# 2225B_VumetreFrequenciel.net
KiCad netlist of a schematic drawn in Altium Designer
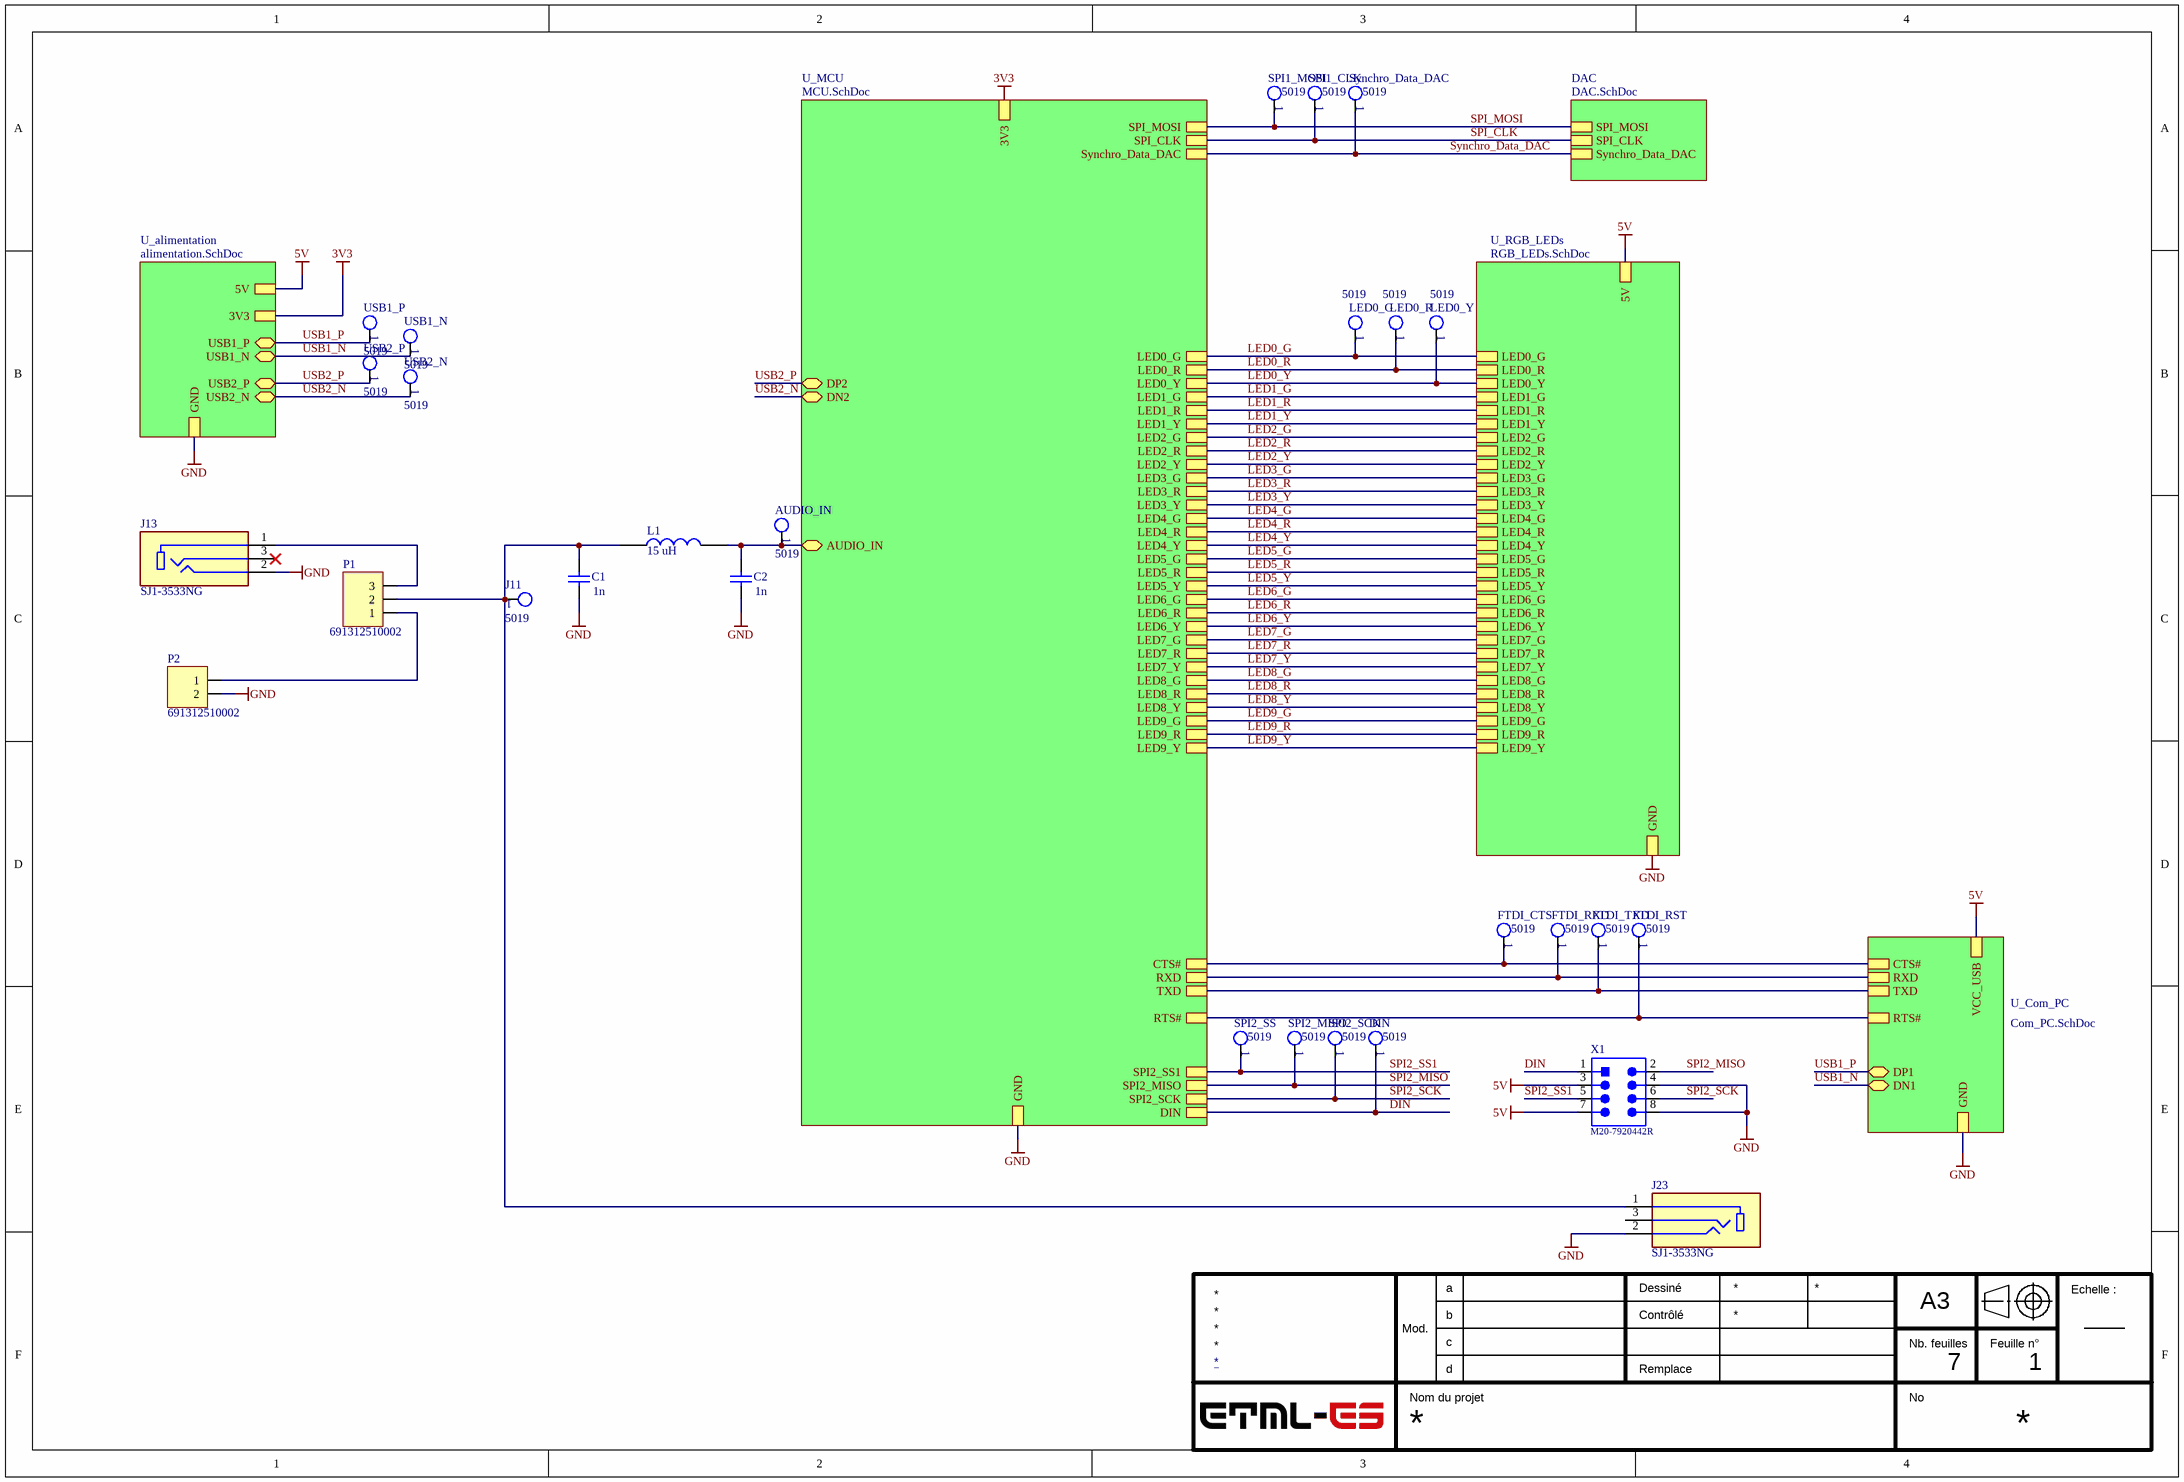
[diagram p0: 2225B_VumetreFrequenciel.SchDoc]

(export (version "E")
  (design (tool "Eeschema 10.0.6"))
  (components
    (comp (ref "AUDIO_IN")
      (value "5019")
      (footprint "KEYSTONE_5019")
      (fields (field (name "MANUFACTURER") "Keystone Electronics"))
      (libsource (lib "2225B_VumetreFrequenciel") (part "CMP-1672-00008-2"))
    )
    (comp (ref "C1")
      (value "1n")
      (footprint "C0805")
      (description "Capacitor")
      (fields (field (name "PUBLISHER") "Altium Limited"))
      (libsource (lib "Miscellaneous Devices") (part "Cap"))
    )
    (comp (ref "C2")
      (value "1n")
      (footprint "C0805")
      (description "Capacitor")
      (fields (field (name "PUBLISHER") "Altium Limited"))
      (libsource (lib "Miscellaneous Devices") (part "Cap"))
    )
    (comp (ref "DIN")
      (value "5019")
      (footprint "KEYSTONE_5019")
      (fields (field (name "MANUFACTURER") "Keystone Electronics"))
      (libsource (lib "2225B_VumetreFrequenciel") (part "CMP-1672-00008-2"))
    )
    (comp (ref "FTDI_CTS")
      (value "5019")
      (footprint "KEYSTONE_5019")
      (fields (field (name "MANUFACTURER") "Keystone Electronics"))
      (libsource (lib "2225B_VumetreFrequenciel") (part "CMP-1672-00008-2"))
    )
    (comp (ref "FTDI_RST")
      (value "5019")
      (footprint "KEYSTONE_5019")
      (fields (field (name "MANUFACTURER") "Keystone Electronics"))
      (libsource (lib "2225B_VumetreFrequenciel") (part "CMP-1672-00008-2"))
    )
    (comp (ref "FTDI_RXD")
      (value "5019")
      (footprint "KEYSTONE_5019")
      (fields (field (name "MANUFACTURER") "Keystone Electronics"))
      (libsource (lib "2225B_VumetreFrequenciel") (part "CMP-1672-00008-2"))
    )
    (comp (ref "FTDI_TXD")
      (value "5019")
      (footprint "KEYSTONE_5019")
      (fields (field (name "MANUFACTURER") "Keystone Electronics"))
      (libsource (lib "2225B_VumetreFrequenciel") (part "CMP-1672-00008-2"))
    )
    (comp (ref "J11")
      (value "5019")
      (footprint "KEYSTONE_5019")
      (fields (field (name "MANUFACTURER") "Keystone Electronics"))
      (libsource (lib "2225B_VumetreFrequenciel") (part "CMP-1672-00008-2"))
    )
    (comp (ref "J13")
      (value "SJ1-3533NG")
      (footprint "CUI_SJ1-3533NG")
      (description "3.5 mm Right-Angle Stereo Jack, 3 Pin PCB Mount, Isolated Ground")
      (fields (field (name "MF") "{'manufacturer': u'CUI'}"))
      (libsource (lib "") (part "SJ1-3533NG_1"))
    )
    (comp (ref "J23")
      (value "SJ1-3533NG")
      (footprint "CUI_SJ1-3533NG")
      (description "3.5 mm Right-Angle Stereo Jack, 3 Pin PCB Mount, Isolated Ground")
      (fields (field (name "MF") "{'manufacturer': u'CUI'}"))
      (libsource (lib "2227_BoiteBruitage") (part "SJ1-3533NG"))
    )
    (comp (ref "L1")
      (value "15 uH")
      (footprint "WE-PD_1210")
      (description "Fixed Inductors 22uH 2.80A 0.028ohms")
      (fields (field (name "MANUFACTURER_PART_NUMBER") "CDRH125NP-220MC"))
      (libsource (lib "TP2_Convertisseur_Courant") (part "CDRH125NP-220MC"))
    )
    (comp (ref "LED0_G")
      (value "5019")
      (footprint "KEYSTONE_5019")
      (fields (field (name "MANUFACTURER") "Keystone Electronics"))
      (libsource (lib "2225B_VumetreFrequenciel") (part "CMP-1672-00008-2"))
    )
    (comp (ref "LED0_R")
      (value "5019")
      (footprint "KEYSTONE_5019")
      (fields (field (name "MANUFACTURER") "Keystone Electronics"))
      (libsource (lib "2225B_VumetreFrequenciel") (part "CMP-1672-00008-2"))
    )
    (comp (ref "LED0_Y")
      (value "5019")
      (footprint "KEYSTONE_5019")
      (fields (field (name "MANUFACTURER") "Keystone Electronics"))
      (libsource (lib "2225B_VumetreFrequenciel") (part "CMP-1672-00008-2"))
    )
    (comp (ref "P1")
      (value "691312510002")
      (footprint "61300311121")
      (description "Header, 3-Pin")
      (fields (field (name "PUBLISHER") "Altium Limited"))
      (libsource (lib "2225B_VumetreFrequenciel") (part "MHDR1X3"))
    )
    (comp (ref "P2")
      (value "691312510002")
      (footprint "LINX_CONBNC002")
      (description "Header, 2-Pin")
      (fields (field (name "PUBLISHER") "Altium Limited"))
      (libsource (lib "2225B_VumetreFrequenciel") (part "MHDR1X2"))
    )
    (comp (ref "SPI1_CLK")
      (value "5019")
      (footprint "KEYSTONE_5019")
      (fields (field (name "MANUFACTURER") "Keystone Electronics"))
      (libsource (lib "2225B_VumetreFrequenciel") (part "CMP-1672-00008-2"))
    )
    (comp (ref "SPI1_MOSI")
      (value "5019")
      (footprint "KEYSTONE_5019")
      (fields (field (name "MANUFACTURER") "Keystone Electronics"))
      (libsource (lib "2225B_VumetreFrequenciel") (part "CMP-1672-00008-2"))
    )
    (comp (ref "SPI2_MISO")
      (value "5019")
      (footprint "KEYSTONE_5019")
      (fields (field (name "MANUFACTURER") "Keystone Electronics"))
      (libsource (lib "2225B_VumetreFrequenciel") (part "CMP-1672-00008-2"))
    )
    (comp (ref "SPI2_SCK")
      (value "5019")
      (footprint "KEYSTONE_5019")
      (fields (field (name "MANUFACTURER") "Keystone Electronics"))
      (libsource (lib "2225B_VumetreFrequenciel") (part "CMP-1672-00008-2"))
    )
    (comp (ref "SPI2_SS")
      (value "5019")
      (footprint "KEYSTONE_5019")
      (fields (field (name "MANUFACTURER") "Keystone Electronics"))
      (libsource (lib "2225B_VumetreFrequenciel") (part "CMP-1672-00008-2"))
    )
    (comp (ref "Synchro_Data_DAC")
      (value "5019")
      (footprint "KEYSTONE_5019")
      (fields (field (name "MANUFACTURER") "Keystone Electronics"))
      (libsource (lib "2225B_VumetreFrequenciel") (part "CMP-1672-00008-2"))
    )
    (comp (ref "USB1_N")
      (value "5019")
      (footprint "KEYSTONE_5019")
      (fields (field (name "MANUFACTURER") "Keystone Electronics"))
      (libsource (lib "2225B_VumetreFrequenciel") (part "CMP-1672-00008-2"))
    )
    (comp (ref "USB1_P")
      (value "5019")
      (footprint "KEYSTONE_5019")
      (fields (field (name "MANUFACTURER") "Keystone Electronics"))
      (libsource (lib "2225B_VumetreFrequenciel") (part "CMP-1672-00008-2"))
    )
    (comp (ref "USB2_N")
      (value "5019")
      (footprint "KEYSTONE_5019")
      (fields (field (name "MANUFACTURER") "Keystone Electronics"))
      (libsource (lib "2225B_VumetreFrequenciel") (part "CMP-1672-00008-2"))
    )
    (comp (ref "USB2_P")
      (value "5019")
      (footprint "KEYSTONE_5019")
      (fields (field (name "MANUFACTURER") "Keystone Electronics"))
      (libsource (lib "2225B_VumetreFrequenciel") (part "CMP-1672-00008-2"))
    )
    (comp (ref "X1")
      (value "M20-7920442R")
      (footprint "610108249121")
      (description "WR-PHD Pin Header, THT, pitch 2.54mm, Dual Row, Angled, 8p")
      (fields
        (field (name "MANUFACTURER PART NUMBER") "61300821021")
        (field (name "MANUFACTURER") "Wurth Elektronik")
      )
      (libsource (lib "2126_AffichageMatriciel") (part "610108249121"))
    )
  )
  (nets
    (net (code "1") (name "/AUDIO_IN") (class "Default")
      (node (ref "AUDIO_IN") (pin "1") (pinfunction "1_1") (pintype "passive"))
      (node (ref "C2") (pin "1") (pinfunction "1_1") (pintype "passive"))
      (node (ref "L1") (pin "2") (pinfunction "2_2") (pintype "passive"))
    )
    (net (code "2") (name "/CTS#") (class "Default")
      (node (ref "FTDI_CTS") (pin "1") (pinfunction "1_1") (pintype "passive"))
    )
    (net (code "3") (name "/DIN") (class "Default")
      (node (ref "DIN") (pin "1") (pinfunction "1_1") (pintype "passive"))
      (node (ref "X1") (pin "1") (pinfunction "1_1") (pintype "passive"))
    )
    (net (code "4") (name "/LED0_G") (class "Default")
      (node (ref "LED0_G") (pin "1") (pinfunction "1_1") (pintype "passive"))
    )
    (net (code "5") (name "/LED0_R") (class "Default")
      (node (ref "LED0_R") (pin "1") (pinfunction "1_1") (pintype "passive"))
    )
    (net (code "6") (name "/LED0_Y") (class "Default")
      (node (ref "LED0_Y") (pin "1") (pinfunction "1_1") (pintype "passive"))
    )
    (net (code "34") (name "/RTS#") (class "Default")
      (node (ref "FTDI_RST") (pin "1") (pinfunction "1_1") (pintype "passive"))
    )
    (net (code "35") (name "/RXD") (class "Default")
      (node (ref "FTDI_RXD") (pin "1") (pinfunction "1_1") (pintype "passive"))
    )
    (net (code "36") (name "/SPI2_MISO") (class "Default")
      (node (ref "SPI2_MISO") (pin "1") (pinfunction "1_1") (pintype "passive"))
      (node (ref "X1") (pin "2") (pinfunction "2_2") (pintype "passive"))
    )
    (net (code "37") (name "/SPI2_SCK") (class "Default")
      (node (ref "SPI2_SCK") (pin "1") (pinfunction "1_1") (pintype "passive"))
      (node (ref "X1") (pin "6") (pinfunction "6_6") (pintype "passive"))
    )
    (net (code "38") (name "/SPI2_SS1") (class "Default")
      (node (ref "SPI2_SS") (pin "1") (pinfunction "1_1") (pintype "passive"))
      (node (ref "X1") (pin "5") (pinfunction "5_5") (pintype "passive"))
    )
    (net (code "39") (name "/SPI_CLK") (class "Default")
      (node (ref "SPI1_CLK") (pin "1") (pinfunction "1_1") (pintype "passive"))
    )
    (net (code "40") (name "/SPI_MOSI") (class "Default")
      (node (ref "SPI1_MOSI") (pin "1") (pinfunction "1_1") (pintype "passive"))
    )
    (net (code "41") (name "/Synchro_Data_DAC") (class "Default")
      (node (ref "Synchro_Data_DAC") (pin "1") (pinfunction "1_1") (pintype "passive"))
    )
    (net (code "42") (name "/TXD") (class "Default")
      (node (ref "FTDI_TXD") (pin "1") (pinfunction "1_1") (pintype "passive"))
    )
    (net (code "43") (name "/USB1_N") (class "Default")
      (node (ref "USB1_N") (pin "1") (pinfunction "1_1") (pintype "passive"))
    )
    (net (code "44") (name "/USB1_P") (class "Default")
      (node (ref "USB1_P") (pin "1") (pinfunction "1_1") (pintype "passive"))
    )
    (net (code "45") (name "/USB2_N") (class "Default")
      (node (ref "USB2_N") (pin "1") (pinfunction "1_1") (pintype "passive"))
    )
    (net (code "46") (name "/USB2_P") (class "Default")
      (node (ref "USB2_P") (pin "1") (pinfunction "1_1") (pintype "passive"))
    )
    (net (code "48") (name "5V") (class "Default")
      (node (ref "X1") (pin "3") (pinfunction "3_3") (pintype "passive"))
      (node (ref "X1") (pin "7") (pinfunction "7_7") (pintype "passive"))
    )
    (net (code "49") (name "GND") (class "Default")
      (node (ref "C1") (pin "2") (pinfunction "2_2") (pintype "passive"))
      (node (ref "C2") (pin "2") (pinfunction "2_2") (pintype "passive"))
      (node (ref "J13") (pin "2") (pinfunction "2_2") (pintype "passive"))
      (node (ref "J23") (pin "2") (pinfunction "2_2") (pintype "passive"))
      (node (ref "P2") (pin "2") (pinfunction "2_2") (pintype "passive"))
      (node (ref "X1") (pin "4") (pinfunction "4_4") (pintype "passive"))
      (node (ref "X1") (pin "8") (pinfunction "8_8") (pintype "passive"))
    )
    (net (code "50") (name "Net-(C1-Pad1)") (class "Default")
      (node (ref "C1") (pin "1") (pinfunction "1_1") (pintype "passive"))
      (node (ref "J11") (pin "1") (pinfunction "1_1") (pintype "passive"))
      (node (ref "J23") (pin "1") (pinfunction "1_1") (pintype "passive"))
      (node (ref "L1") (pin "1") (pinfunction "1_1") (pintype "passive"))
      (node (ref "P1") (pin "2") (pinfunction "2_2") (pintype "passive"))
    )
    (net (code "51") (name "Net-(J13-Pad1)") (class "Default")
      (node (ref "J13") (pin "1") (pinfunction "1_1") (pintype "passive"))
      (node (ref "P1") (pin "3") (pinfunction "3_3") (pintype "passive"))
    )
    (net (code "52") (name "Net-(P1-Pad1)") (class "Default")
      (node (ref "P1") (pin "1") (pinfunction "1_1") (pintype "passive"))
      (node (ref "P2") (pin "1") (pinfunction "1_1") (pintype "passive"))
    )
    (net (code "53") (name "unconnected-(J13-Pad3)") (class "Default")
      (node (ref "J13") (pin "3") (pinfunction "3_3") (pintype "passive+no_connect"))
    )
    (net (code "54") (name "unconnected-(J23-Pad3)") (class "Default")
      (node (ref "J23") (pin "3") (pinfunction "3_3") (pintype "passive"))
    )
  )
)
